# A-Power.net
KiCad netlist of a schematic drawn in Altium Designer
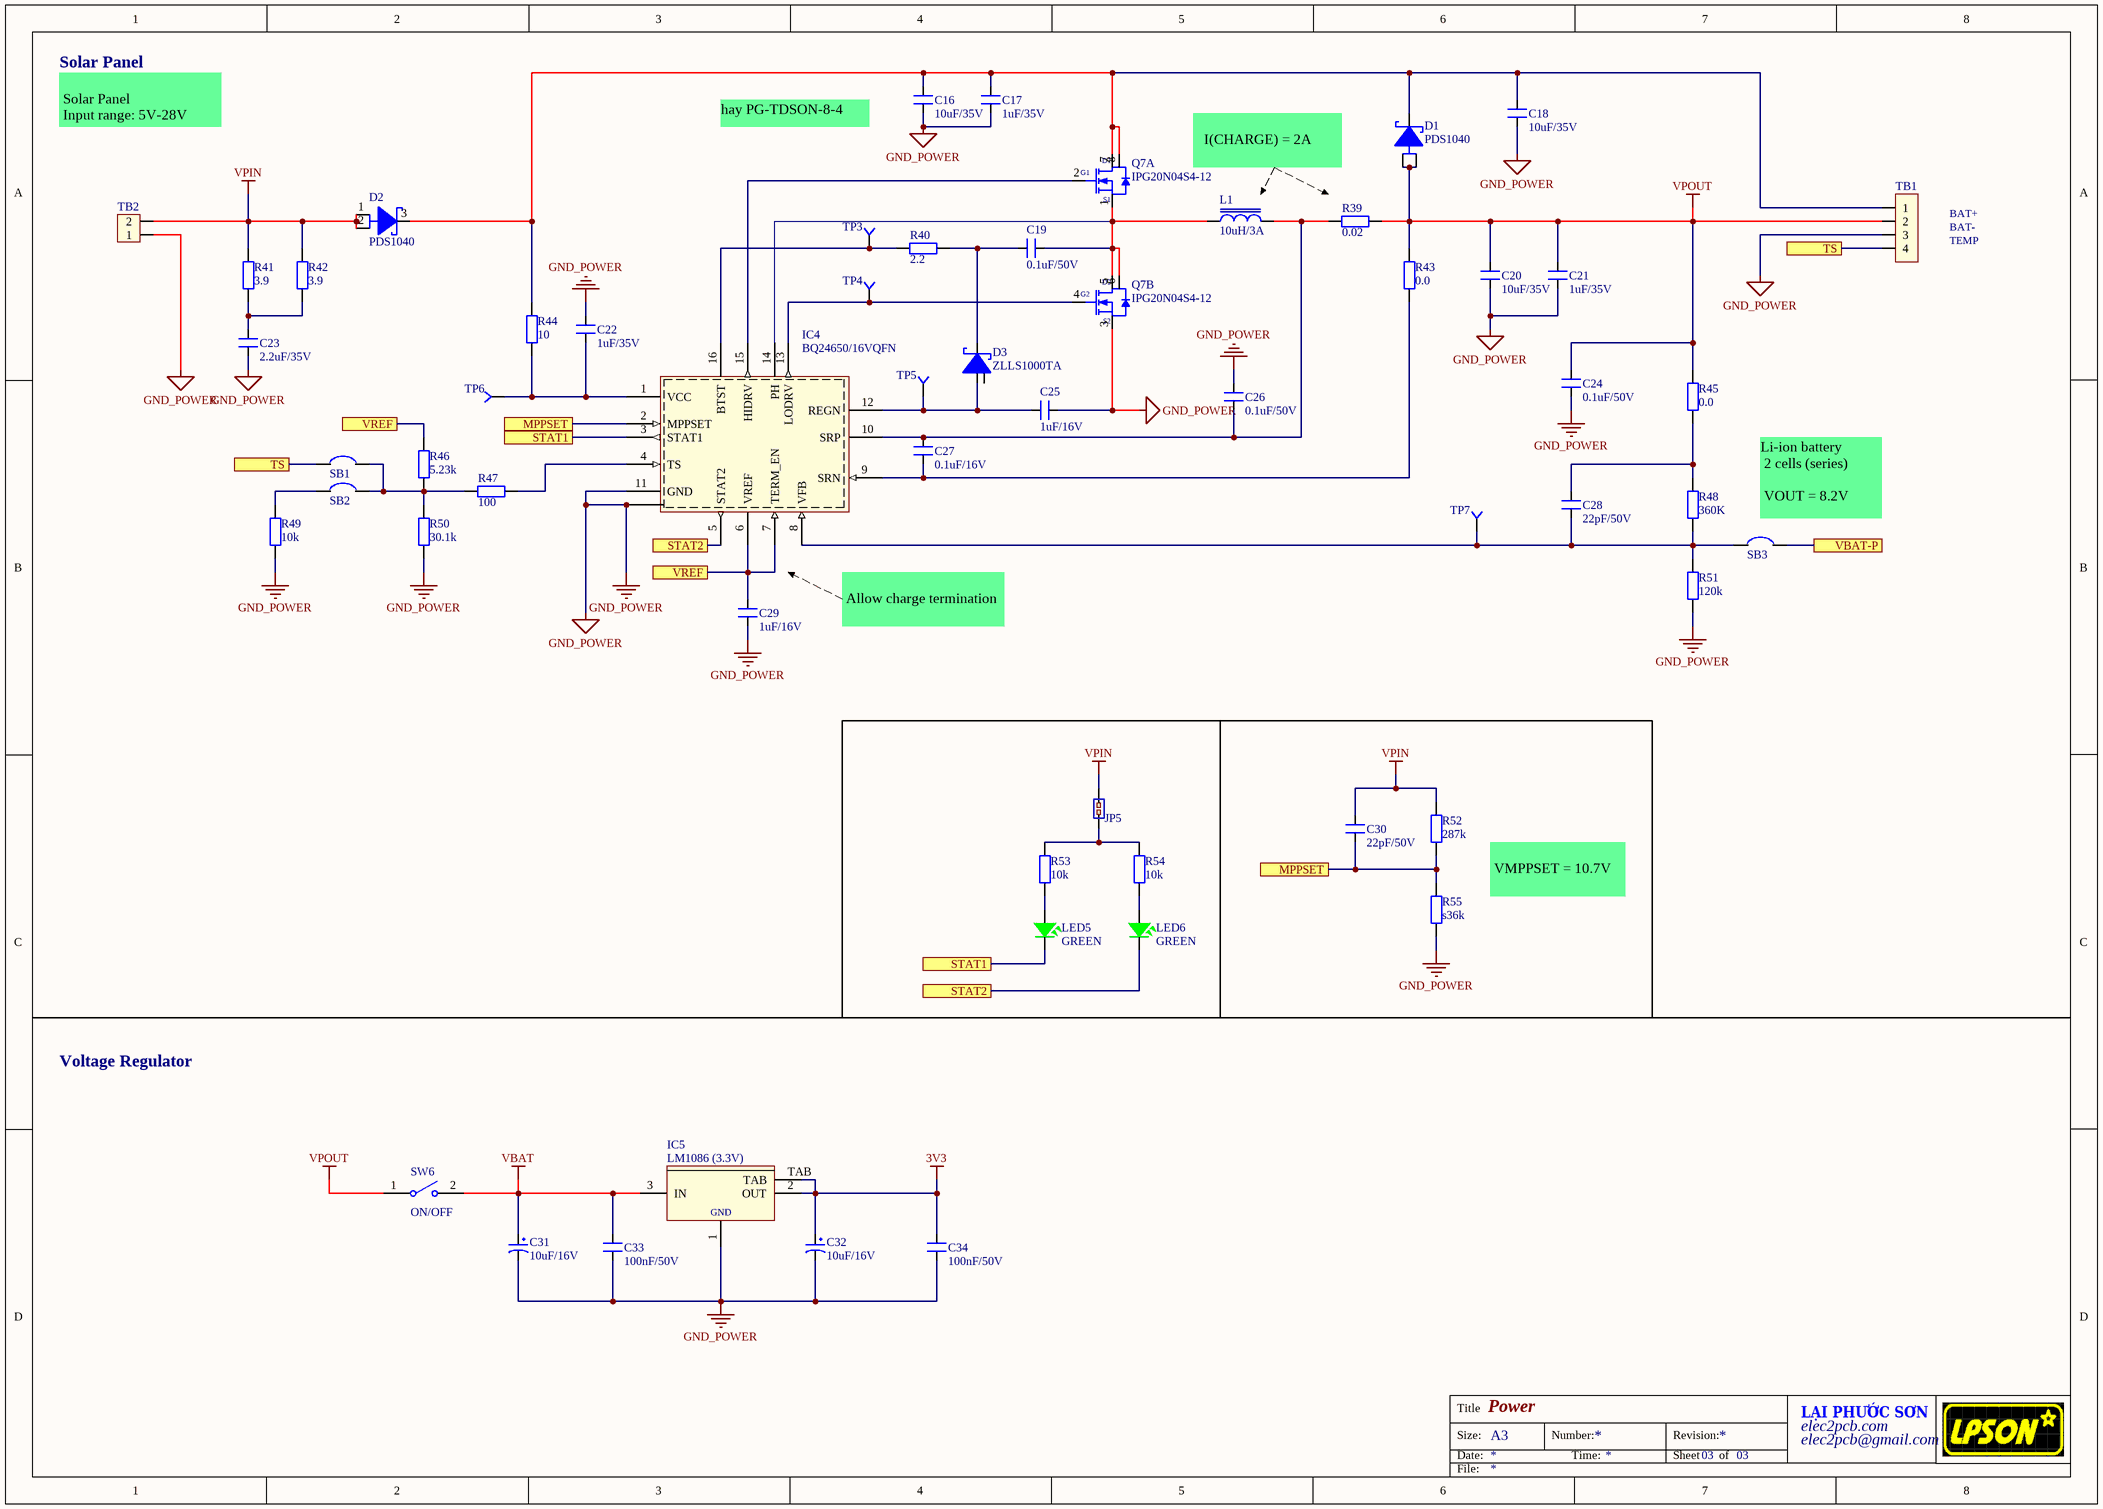
[diagram p0: A-Power.SchDoc]

(export (version "E")
  (design (tool "Eeschema 10.0.6"))
  (components
    (comp (ref "C16")
      (value "10uF/35V")
      (footprint "CAP_CERA_C3216(CC1206INCH)")
      (description "CAP CER 10UF 35V X7R 1206")
      (fields
        (field (name "MANUFACTURER") "Taiyo Yuden")
        (field (name "MANUFACTURER PART NUMBER") "GMK316AB7106KL-TR")
      )
      (libsource (lib "Tran Tuan") (part "CAP-CER/10uF/35V/X7R-1206"))
    )
    (comp (ref "C17")
      (value "1uF/35V")
      (footprint "CAP_CERA_C2012(CC0805INCH)")
      (description "CAP CER 1UF 35V X7R 0805")
      (fields
        (field (name "MANUFACTURER") "Taiyo Yuden")
        (field (name "MANUFACTURER PART NUMBER") "GMK212B7105KG-T")
      )
      (libsource (lib "Tran Tuan") (part "CAP-CER/1uF/35V/X7R/0805"))
    )
    (comp (ref "C18")
      (value "10uF/35V")
      (footprint "CAP_CERA_C3216(CC1206INCH)")
      (description "CAP CER 10UF 35V X7R 1206")
      (fields
        (field (name "MANUFACTURER") "Taiyo Yuden")
        (field (name "MANUFACTURER PART NUMBER") "GMK316AB7106KL-TR")
      )
      (libsource (lib "Tran Tuan") (part "CAP-CER/10uF/35V/X7R-1206"))
    )
    (comp (ref "C19")
      (value "0.1uF/50V")
      (footprint "CAP_CERA_C1608(CC0603INCH)")
      (description "CAP CER 0.1UF 50V X7R 0603")
      (fields
        (field (name "MANUFACTURER") "Kemet")
        (field (name "MANUFACTURER PART NUMBER") "C0603X104K5RACTU")
      )
      (libsource (lib "Tran Tuan") (part "CAP-CER/0.1uF/50V/X7R/0603"))
    )
    (comp (ref "C20")
      (value "10uF/35V")
      (footprint "CAP_CERA_C3216(CC1206INCH)")
      (description "CAP CER 10UF 35V X7R 1206")
      (fields
        (field (name "MANUFACTURER") "Taiyo Yuden")
        (field (name "MANUFACTURER PART NUMBER") "GMK316AB7106KL-TR")
      )
      (libsource (lib "Tran Tuan") (part "CAP-CER/10uF/35V/X7R-1206"))
    )
    (comp (ref "C21")
      (value "1uF/35V")
      (footprint "CAP_CERA_C2012(CC0805INCH)")
      (description "CAP CER 1UF 35V X7R 0805")
      (fields
        (field (name "MANUFACTURER") "Taiyo Yuden")
        (field (name "MANUFACTURER PART NUMBER") "GMK212B7105KG-T")
      )
      (libsource (lib "Tran Tuan") (part "CAP-CER/1uF/35V/X7R/0805"))
    )
    (comp (ref "C22")
      (value "1uF/35V")
      (footprint "CAP_CERA_C2012(CC0805INCH)")
      (description "CAP CER 1UF 35V X7R 0805")
      (fields
        (field (name "MANUFACTURER") "Taiyo Yuden")
        (field (name "MANUFACTURER PART NUMBER") "GMK212B7105KG-T")
      )
      (libsource (lib "Tran Tuan") (part "CAP-CER/1uF/35V/X7R/0805"))
    )
    (comp (ref "C23")
      (value "2.2uF/35V")
      (footprint "CAP_CERA_C3225(CC1210)")
      (description "CAP CER 2.2UF 35V X7R 1210")
      (fields
        (field (name "MANUFACTURER") "Taiyo Yuden")
        (field (name "MANUFACTURER PART NUMBER") "GMK325B7225KNHT")
      )
      (libsource (lib "Tran Tuan") (part "CAP-CER/2.2uF/35V/X7R/1210"))
    )
    (comp (ref "C24")
      (value "0.1uF/50V")
      (footprint "CAP_CERA_C1608(CC0603INCH)")
      (description "CAP CER 0.1UF 50V X7R 0603")
      (fields
        (field (name "MANUFACTURER") "Kemet")
        (field (name "MANUFACTURER PART NUMBER") "C0603X104K5RACTU")
      )
      (libsource (lib "Tran Tuan") (part "CAP-CER/0.1uF/50V/X7R/0603"))
    )
    (comp (ref "C25")
      (value "1uF/16V")
      (footprint "CAP_CERA_C2012(CC0805INCH)")
      (description "CAP CER 1UF 16V X7R 0805")
      (fields
        (field (name "MANUFACTURER") "Kemet")
        (field (name "MANUFACTURER PART NUMBER") "C0805C105K4RACTU")
      )
      (libsource (lib "Tran Tuan") (part "CAP-CER/1uF/16V/X7R/0805"))
    )
    (comp (ref "C26")
      (value "0.1uF/50V")
      (footprint "CAP_CERA_C1608(CC0603INCH)")
      (description "CAP CER 0.1UF 50V X7R 0603")
      (fields
        (field (name "MANUFACTURER") "Kemet")
        (field (name "MANUFACTURER PART NUMBER") "C0603X104K5RACTU")
      )
      (libsource (lib "Tran Tuan") (part "CAP-CER/0.1uF/50V/X7R/0603"))
    )
    (comp (ref "C27")
      (value "0.1uF/16V")
      (footprint "CAP_CERA_C1608(CC0603INCH)")
      (description "CAP CER 0.1UF 16V X7R 0603")
      (fields
        (field (name "MANUFACTURER") "Yageo")
        (field (name "MANUFACTURER PART NUMBER") "CC0603KRX7R7BB104")
      )
      (libsource (lib "Tran Tuan") (part "CAP-CER/0.1uF/16V/X7R/0603"))
    )
    (comp (ref "C28")
      (value "22pF/50V")
      (footprint "CAP_CERA_C1608(CC0603INCH)")
      (description "CAP CER 22PF 50V X7R 0603")
      (fields
        (field (name "MANUFACTURER") "AVX Corporation")
        (field (name "MANUFACTURER PART NUMBER") "06035C220JAT2A")
      )
      (libsource (lib "Tran Tuan") (part "CAP-CER/22pF/50V/X7R/0603"))
    )
    (comp (ref "C29")
      (value "1uF/16V")
      (footprint "CAP_CERA_C2012(CC0805INCH)")
      (description "CAP CER 1UF 16V X7R 0805")
      (fields
        (field (name "MANUFACTURER") "Kemet")
        (field (name "MANUFACTURER PART NUMBER") "C0805C105K4RACTU")
      )
      (libsource (lib "Tran Tuan") (part "CAP-CER/1uF/16V/X7R/0805"))
    )
    (comp (ref "C30")
      (value "22pF/50V")
      (footprint "CAP_CERA_C1608(CC0603INCH)")
      (description "CAP CER 22PF 50V X7R 0603")
      (fields
        (field (name "MANUFACTURER") "AVX Corporation")
        (field (name "MANUFACTURER PART NUMBER") "06035C220JAT2A")
      )
      (libsource (lib "Tran Tuan") (part "CAP-CER/22pF/50V/X7R/0603"))
    )
    (comp (ref "C31")
      (value "10uF/16V")
      (footprint "CAP_CERA_C3216(CC1206INCH)")
      (description "CAP TANT 10UF 16V 10% 1206")
      (fields
        (field (name "MANUFACTURER") "Kemet")
        (field (name "MANUFACTURER PART NUMBER") "T491A106K016AT")
      )
      (libsource (lib "Tran Tuan") (part "CAP-TANT/10uF/16V/1206"))
    )
    (comp (ref "C32")
      (value "10uF/16V")
      (footprint "CAP_CERA_C3216(CC1206INCH)")
      (description "CAP TANT 10UF 16V 10% 1206")
      (fields
        (field (name "MANUFACTURER") "Kemet")
        (field (name "MANUFACTURER PART NUMBER") "T491A106K016AT")
      )
      (libsource (lib "Tran Tuan") (part "CAP-TANT/10uF/16V/1206"))
    )
    (comp (ref "C33")
      (value "100nF/50V")
      (footprint "CAP_CERA_C2012(CC0805INCH)")
      (description "CAP CER 0.1UF 50V X7R 0805")
      (fields
        (field (name "MANUFACTURER") "AVX Corporation")
        (field (name "MANUFACTURER PART NUMBER") "08055C104KAT2A")
      )
      (libsource (lib "Tran Tuan") (part "CAP-CER/100nF/50V/X7R-0805"))
    )
    (comp (ref "C34")
      (value "100nF/50V")
      (footprint "CAP_CERA_C2012(CC0805INCH)")
      (description "CAP CER 0.1UF 50V X7R 0805")
      (fields
        (field (name "MANUFACTURER") "AVX Corporation")
        (field (name "MANUFACTURER PART NUMBER") "08055C104KAT2A")
      )
      (libsource (lib "Tran Tuan") (part "CAP-CER/100nF/50V/X7R-0805"))
    )
    (comp (ref "D1")
      (value "PDS1040")
      (footprint "PDS1040")
      (description "DIODE SCHOTTKY 40V 10A POWERDI5")
      (fields
        (field (name "MANUFACTURER") "Diodes Incorporated")
        (field (name "MANUFACTURER PART NUMBER") "PDS1040-13")
      )
      (libsource (lib "") (part "DIODE-PDS1040/POWERDI5_1"))
    )
    (comp (ref "D2")
      (value "PDS1040")
      (footprint "PDS1040")
      (description "DIODE SCHOTTKY 40V 10A POWERDI5")
      (fields
        (field (name "MANUFACTURER") "Diodes Incorporated")
        (field (name "MANUFACTURER PART NUMBER") "PDS1040-13")
      )
      (libsource (lib "Tran Tuan") (part "DIODE-PDS1040/POWERDI5"))
    )
    (comp (ref "D3")
      (value "ZLLS1000TA")
      (footprint "ZLLS1000")
      (description "DIODE SCHOTTKY 40V 1.16A SOT23-3")
      (fields (field (name "MANUFACTURER") "Diodes Incorporated"))
      (libsource (lib "Tran Tuan") (part "DIODE-ZLLS1000TA/SOT23-3"))
    )
    (comp (ref "IC4")
      (value "BQ24650/16VQFN")
      (footprint "BQ24650-16VQFN")
      (description "IC SYNC SW-MODE BAT CHRGR 16VQFN")
      (fields
        (field (name "MANUFACTURER") "Texas Instruments")
        (field (name "MANUFACTURER PART NUMBER") "BQ24650RVAT")
      )
      (libsource (lib "Tran Tuan") (part "BQ24650/16VQFN"))
    )
    (comp (ref "IC5")
      (value "LM1086 (3.3V)")
      (footprint "LM1086")
      (description "IC REG LDO 3.3V 1.5A DDPAK")
      (fields
        (field (name "MANUFACTURER") "Texas Instruments")
        (field (name "MANUFACTURER PART NUMBER") "LM1086CS-3.3/NOPB")
      )
      (libsource (lib "Tran Tuan") (part "LM1086CS-3.3/NOPB"))
    )
    (comp (ref "JP5")
      (value "JP2-ShortingJumper")
      (footprint "Header_2")
      (description "2.54mm 2-Pin Shorting Jumper")
      (libsource (lib "Tran Tuan") (part "JP2-ShortingJumper"))
    )
    (comp (ref "L1")
      (value "10uH/3A")
      (footprint "IHLP-2525CZ-01")
      (description "FIXED IND 10UH 3A 105mOHM SMD")
      (fields
        (field (name "MANUFACTURER") "Vishay Dale")
        (field (name "MANUFACTURER PART NUMBER") "IHLP2525CZER100M01")
      )
      (libsource (lib "Tran Tuan") (part "IND-10uH/3A/105mOHM"))
    )
    (comp (ref "LED5")
      (value "GREEN")
      (footprint "Led 0805G")
      (description "LED GREEN CLEAR 0805 SMD")
      (fields
        (field (name "MANUFACTURER") "Lite-On Inc.")
        (field (name "MANUFACTURER PART NUMBER") "LTST-C171GKT")
      )
      (libsource (lib "Tran Tuan") (part "LED-GREEN/CLEAR/0805"))
    )
    (comp (ref "LED6")
      (value "GREEN")
      (footprint "Led 0805G")
      (description "LED GREEN CLEAR 0805 SMD")
      (fields
        (field (name "MANUFACTURER") "Lite-On Inc.")
        (field (name "MANUFACTURER PART NUMBER") "LTST-C171GKT")
      )
      (libsource (lib "Tran Tuan") (part "LED-GREEN/CLEAR/0805"))
    )
    (comp (ref "Q7")
      (value "IPG20N04S4-12")
      (footprint "PG-TDSON-8-4")
      (description "MOSFE,T 2N-CH, 40V 20A TDSON-8 OptiMOS-T2")
      (fields (field (name "MANUFACTURER") "Infineon"))
      (libsource (lib "Tran Tuan") (part "MOSFET-IPG20N04S4/TDSON8"))
    )
    (comp (ref "R39")
      (value "~")
      (footprint "RES-1206-3216MM")
      (description "RES SMD 0.02 OHM 1% 1W 1206")
      (fields
        (field (name "MANUFACTURER") "Vishay Dale")
        (field (name "MANUFACTURER PART NUMBER") "WSLP1206R0200FEA")
        (field (name "RESISTANCE (OHMS)") "0.02")
      )
      (libsource (lib "Tran Tuan") (part "RES-1206/±1%"))
    )
    (comp (ref "R40")
      (value "~")
      (footprint "RESC2012(0805)")
      (description "RES SMD 2.2 OHM 5% 1/8W 0805")
      (fields
        (field (name "MANUFACTURER") "Panasonic Electronic Components")
        (field (name "MANUFACTURER PART NUMBER") "ERJ-6GEYJ2R2V")
        (field (name "RESISTANCE (OHMS)") "2.2")
      )
      (libsource (lib "") (part "RES-0805/±5%_1"))
    )
    (comp (ref "R41")
      (value "~")
      (footprint "RES-1206-3216MM")
      (description "RES SMD 3.9 OHM 1% 1/4W 1206")
      (fields
        (field (name "MANUFACTURER") "Panasonic Electronic Components")
        (field (name "MANUFACTURER PART NUMBER") "ERJ-8RQF3R9V")
        (field (name "RESISTANCE (OHMS)") "3.9")
      )
      (libsource (lib "Tran Tuan") (part "RES-1206/±5%"))
    )
    (comp (ref "R42")
      (value "~")
      (footprint "RES-1206-3216MM")
      (description "RES SMD 3.9 OHM 1% 1/4W 1206")
      (fields
        (field (name "MANUFACTURER") "Panasonic Electronic Components")
        (field (name "MANUFACTURER PART NUMBER") "ERJ-8RQF3R9V")
        (field (name "RESISTANCE (OHMS)") "3.9")
      )
      (libsource (lib "Tran Tuan") (part "RES-1206/±5%"))
    )
    (comp (ref "R43")
      (value "~")
      (footprint "RESC2012(0805)")
      (description "RES SMD 0.0 OHM JUMPER 1/8W 0805")
      (fields
        (field (name "MANUFACTURER") "Yageo")
        (field (name "MANUFACTURER PART NUMBER") "RC0805JR-070RL")
        (field (name "RESISTANCE (OHMS)") "0.0")
      )
      (libsource (lib "Tran Tuan") (part "RES-0805/±5%"))
    )
    (comp (ref "R44")
      (value "~")
      (footprint "RESC2012(0805)")
      (description "RES SMD 10 OHM 5% 1/8W 0805")
      (fields
        (field (name "MANUFACTURER") "Yageo")
        (field (name "MANUFACTURER PART NUMBER") "RC0805JR-0710RL")
        (field (name "RESISTANCE (OHMS)") "10")
      )
      (libsource (lib "Tran Tuan") (part "RES-0805/±5%"))
    )
    (comp (ref "R45")
      (value "~")
      (footprint "RESC2012(0805)")
      (description "RES SMD 0.0 OHM JUMPER 1/8W 0805")
      (fields
        (field (name "MANUFACTURER") "Yageo")
        (field (name "MANUFACTURER PART NUMBER") "RC0805JR-070RL")
        (field (name "RESISTANCE (OHMS)") "0.0")
      )
      (libsource (lib "Tran Tuan") (part "RES-0805/±5%"))
    )
    (comp (ref "R46")
      (value "~")
      (footprint "RESC2012(0805)")
      (description "RES SMD 5.23K OHM 1% 1/8W 0805")
      (fields
        (field (name "MANUFACTURER") "Panasonic Electronic Components")
        (field (name "MANUFACTURER PART NUMBER") "ERJ-6ENF5231V")
        (field (name "RESISTANCE (OHMS)") "5.23k")
      )
      (libsource (lib "") (part "RES-0805/±1%_1"))
    )
    (comp (ref "R47")
      (value "~")
      (footprint "RESC2012(0805)")
      (description "RES SMD 100 OHM 5% 1/8W 0805")
      (fields
        (field (name "MANUFACTURER") "Panasonic Electronic Components")
        (field (name "MANUFACTURER PART NUMBER") "ERJ-6GEYJ101V")
        (field (name "RESISTANCE (OHMS)") "100")
      )
      (libsource (lib "") (part "RES-0805/±5%_1"))
    )
    (comp (ref "R48")
      (value "360K")
      (footprint "RESC2012(0805)")
      (description "RES SMD 360K OHM 1% 1/8W 0805")
      (fields
        (field (name "MANUFACTURER") "Yageo")
        (field (name "MANUFACTURER PART NUMBER") "RC0805FR-07360KL")
      )
      (libsource (lib "Tran Tuan") (part "RES-0805/±1%"))
    )
    (comp (ref "R49")
      (value "~")
      (footprint "RESC2012(0805)")
      (description "RES SMD 10K OHM 5% 1/8W 0805")
      (fields
        (field (name "MANUFACTURER") "Yageo")
        (field (name "MANUFACTURER PART NUMBER") "RC0805JR-0710KL")
        (field (name "RESISTANCE (OHMS)") "10k")
      )
      (libsource (lib "Tran Tuan") (part "RES-0805/±5%"))
    )
    (comp (ref "R50")
      (value "~")
      (footprint "RESC2012(0805)")
      (description "RES SMD 30.1K OHM 1% 1/8W 0805")
      (fields
        (field (name "MANUFACTURER") "Yageo")
        (field (name "MANUFACTURER PART NUMBER") "RC0805FR-0730K1L")
        (field (name "RESISTANCE (OHMS)") "30.1k")
      )
      (libsource (lib "") (part "RES-0805/±1%_1"))
    )
    (comp (ref "R51")
      (value "~")
      (footprint "RESC2012(0805)")
      (description "RES SMD 120K OHM 1% 1/8W 0805")
      (fields
        (field (name "MANUFACTURER") "Yageo")
        (field (name "MANUFACTURER PART NUMBER") "RC0805FR-07120KL")
        (field (name "RESISTANCE (OHMS)") "120k")
      )
      (libsource (lib "") (part "RES-0805/±1%_1"))
    )
    (comp (ref "R52")
      (value "~")
      (footprint "RESC2012(0805)")
      (description "RES SMD 287K OHM 1% 1/8W 0805")
      (fields
        (field (name "MANUFACTURER") "Panasonic Electronic Components")
        (field (name "MANUFACTURER PART NUMBER") "ERJ-6ENF2873V")
        (field (name "RESISTANCE (OHMS)") "287k")
      )
      (libsource (lib "") (part "RES-0805/±1%_1"))
    )
    (comp (ref "R53")
      (value "~")
      (footprint "RESC2012(0805)")
      (description "RES SMD 10K OHM 5% 1/8W 0805")
      (fields
        (field (name "MANUFACTURER") "Yageo")
        (field (name "MANUFACTURER PART NUMBER") "RC0805JR-0710KL")
        (field (name "RESISTANCE (OHMS)") "10k")
      )
      (libsource (lib "Tran Tuan") (part "RES-0805/±5%"))
    )
    (comp (ref "R54")
      (value "~")
      (footprint "RESC2012(0805)")
      (description "RES SMD 10K OHM 5% 1/8W 0805")
      (fields
        (field (name "MANUFACTURER") "Yageo")
        (field (name "MANUFACTURER PART NUMBER") "RC0805JR-0710KL")
        (field (name "RESISTANCE (OHMS)") "10k")
      )
      (libsource (lib "Tran Tuan") (part "RES-0805/±5%"))
    )
    (comp (ref "R55")
      (value "~")
      (footprint "RESC2012(0805)")
      (description "RES SMD 36K OHM 1% 1/8W 0805")
      (fields
        (field (name "MANUFACTURER") "Panasonic Electronic Components")
        (field (name "MANUFACTURER PART NUMBER") "ERJ-6ENF3602V")
        (field (name "RESISTANCE (OHMS)") "s36k")
      )
      (libsource (lib "Tran Tuan") (part "RES-0805/±1%"))
    )
    (comp (ref "SB1")
      (value "Connect")
      (footprint "head PAD")
      (description "Jumper, Connector, 2-pad")
      (libsource (lib "Tran Tuan") (part "Connector-SB"))
    )
    (comp (ref "SB2")
      (value "Connect")
      (footprint "head PAD")
      (description "Jumper, Connector, 2-pad")
      (libsource (lib "Tran Tuan") (part "Connector-SB"))
    )
    (comp (ref "SB3")
      (value "Connect")
      (footprint "head PAD")
      (description "Jumper, Connector, 2-pad")
      (libsource (lib "Tran Tuan") (part "Connector-SB"))
    )
    (comp (ref "SW6")
      (value "ON/OFF")
      (footprint "SW-POWER")
      (description "SWITCH ROCKER SPST 16A 125V")
      (fields
        (field (name "MANUFACTURER") "TE Connectivity Alcoswitch Switches")
        (field (name "MANUFACTURER PART NUMBER") "PRASA1-16F-BB0BW")
      )
      (libsource (lib "Tran Tuan") (part "SW-ROCKER/SPST/16A"))
    )
    (comp (ref "TB1")
      (value "TERM BLOCK")
      (footprint "MKDS-DOMINO-4-PIN")
      (description "TERM BLOCK 4POS 3.81MM PCB GRN")
      (fields
        (field (name "MANUFACTURER") "Phoenix Contact")
        (field (name "MANUFACTURER PART NUMBER") "1727036")
      )
      (libsource (lib "Tran Tuan") (part "TERM/3.81MM/4POS/GREEN"))
    )
    (comp (ref "TB2")
      (value "TERM BLOCK")
      (footprint "MKDS-DOMINO-2-PIN")
      (description "TERM BLOCK 2POS 3.81MM PCB GRN")
      (fields
        (field (name "MANUFACTURER") "Phoenix Contact")
        (field (name "MANUFACTURER PART NUMBER") "1727010")
      )
      (libsource (lib "Tran Tuan") (part "TERM/3.81MM/2POS/GREEN"))
    )
    (comp (ref "TP3")
      (value "Test Point")
      (footprint "Test_point_VIA06")
      (description "Test Point, Pad, Hole")
      (libsource (lib "Tran Tuan") (part "Connector-TP"))
    )
    (comp (ref "TP4")
      (value "Test Point")
      (footprint "Test_point_VIA06")
      (description "Test Point, Pad, Hole")
      (libsource (lib "Tran Tuan") (part "Connector-TP"))
    )
    (comp (ref "TP5")
      (value "Test Point")
      (footprint "Test_point_VIA06")
      (description "Test Point, Pad, Hole")
      (libsource (lib "Tran Tuan") (part "Connector-TP"))
    )
    (comp (ref "TP6")
      (value "Test Point")
      (footprint "Test_point_VIA06")
      (description "Test Point, Pad, Hole")
      (libsource (lib "Tran Tuan") (part "Connector-TP"))
    )
    (comp (ref "TP7")
      (value "Test Point")
      (footprint "Test_point_VIA06")
      (description "Test Point, Pad, Hole")
      (libsource (lib "Tran Tuan") (part "Connector-TP"))
    )
  )
  (nets
    (net (code "1") (name "/MPPSET") (class "Default")
      (node (ref "C30") (pin "2") (pinfunction "2_2") (pintype "passive"))
      (node (ref "IC4") (pin "2") (pinfunction "MPPSET_2") (pintype "input"))
      (node (ref "R52") (pin "2") (pinfunction "2_2") (pintype "passive"))
      (node (ref "R55") (pin "2") (pinfunction "2_2") (pintype "passive"))
    )
    (net (code "2") (name "/STAT1") (class "Default")
      (node (ref "IC4") (pin "3") (pinfunction "STAT1_3") (pintype "output"))
      (node (ref "LED5") (pin "2") (pinfunction "K_2") (pintype "passive"))
    )
    (net (code "3") (name "/STAT2") (class "Default")
      (node (ref "IC4") (pin "5") (pinfunction "STAT2_5") (pintype "output"))
      (node (ref "LED6") (pin "2") (pinfunction "K_2") (pintype "passive"))
    )
    (net (code "4") (name "/TS") (class "Default")
      (node (ref "SB1") (pin "2") (pinfunction "2_2") (pintype "passive"))
      (node (ref "TB1") (pin "4") (pinfunction "4_4") (pintype "passive"))
    )
    (net (code "5") (name "/VBAT-P") (class "Default")
      (node (ref "SB3") (pin "1") (pinfunction "1_1") (pintype "passive"))
    )
    (net (code "6") (name "/VREF") (class "Default")
      (node (ref "C29") (pin "2") (pinfunction "2_2") (pintype "passive"))
      (node (ref "IC4") (pin "6") (pinfunction "VREF_6") (pintype "power_in"))
      (node (ref "IC4") (pin "7") (pinfunction "TERM_EN_7") (pintype "input"))
      (node (ref "R46") (pin "1") (pinfunction "1_1") (pintype "passive"))
    )
    (net (code "7") (name "3V3") (class "Default")
      (node (ref "C32") (pin "1") (pinfunction "1_1") (pintype "passive"))
      (node (ref "C34") (pin "1") (pinfunction "1_1") (pintype "passive"))
      (node (ref "IC5") (pin "2") (pinfunction "OUT_2") (pintype "power_in"))
      (node (ref "IC5") (pin "TAB") (pinfunction "TAB_TAB") (pintype "power_in"))
    )
    (net (code "8") (name "GND_POWER") (class "Default")
      (node (ref "C16") (pin "2") (pinfunction "2_2") (pintype "passive"))
      (node (ref "C17") (pin "2") (pinfunction "2_2") (pintype "passive"))
      (node (ref "C18") (pin "2") (pinfunction "2_2") (pintype "passive"))
      (node (ref "C20") (pin "2") (pinfunction "2_2") (pintype "passive"))
      (node (ref "C21") (pin "2") (pinfunction "2_2") (pintype "passive"))
      (node (ref "C22") (pin "2") (pinfunction "2_2") (pintype "passive"))
      (node (ref "C23") (pin "2") (pinfunction "2_2") (pintype "passive"))
      (node (ref "C24") (pin "1") (pinfunction "1_1") (pintype "passive"))
      (node (ref "C25") (pin "1") (pinfunction "1_1") (pintype "passive"))
      (node (ref "C26") (pin "2") (pinfunction "2_2") (pintype "passive"))
      (node (ref "C29") (pin "1") (pinfunction "1_1") (pintype "passive"))
      (node (ref "C31") (pin "2") (pinfunction "2_2") (pintype "passive"))
      (node (ref "C32") (pin "2") (pinfunction "2_2") (pintype "passive"))
      (node (ref "C33") (pin "2") (pinfunction "2_2") (pintype "passive"))
      (node (ref "C34") (pin "2") (pinfunction "2_2") (pintype "passive"))
      (node (ref "IC4") (pin "11") (pinfunction "GND_11") (pintype "power_in"))
      (node (ref "IC4") (pin "PAD") (pinfunction "PAD_PAD") (pintype "power_in"))
      (node (ref "IC5") (pin "1") (pinfunction "GND_1") (pintype "power_in"))
      (node (ref "Q7") (pin "3") (pinfunction "S2_3") (pintype "passive"))
      (node (ref "R49") (pin "2") (pinfunction "2_2") (pintype "passive"))
      (node (ref "R50") (pin "2") (pinfunction "2_2") (pintype "passive"))
      (node (ref "R51") (pin "2") (pinfunction "2_2") (pintype "passive"))
      (node (ref "R55") (pin "1") (pinfunction "1_1") (pintype "passive"))
      (node (ref "TB1") (pin "3") (pinfunction "3_3") (pintype "passive"))
      (node (ref "TB2") (pin "1") (pinfunction "1_1") (pintype "passive"))
    )
    (net (code "9") (name "Net-(C23-Pad1)") (class "Default")
      (node (ref "C23") (pin "1") (pinfunction "1_1") (pintype "passive"))
      (node (ref "R41") (pin "2") (pinfunction "2_2") (pintype "passive"))
      (node (ref "R42") (pin "2") (pinfunction "2_2") (pintype "passive"))
    )
    (net (code "10") (name "Net-(C28-Pad1)") (class "Default")
      (node (ref "C28") (pin "1") (pinfunction "1_1") (pintype "passive"))
      (node (ref "R45") (pin "2") (pinfunction "2_2") (pintype "passive"))
      (node (ref "R48") (pin "2") (pinfunction "2_2") (pintype "passive"))
    )
    (net (code "11") (name "Net-(D1-K)") (class "Default")
      (node (ref "C16") (pin "1") (pinfunction "1_1") (pintype "passive"))
      (node (ref "C17") (pin "1") (pinfunction "1_1") (pintype "passive"))
      (node (ref "C18") (pin "1") (pinfunction "1_1") (pintype "passive"))
      (node (ref "D1") (pin "3") (pinfunction "K_3") (pintype "passive"))
      (node (ref "D2") (pin "3") (pinfunction "K_3") (pintype "passive"))
      (node (ref "Q7") (pin "7") (pinfunction "D1_7") (pintype "passive"))
      (node (ref "Q7") (pin "8") (pinfunction "D1_8") (pintype "passive"))
      (node (ref "R44") (pin "1") (pinfunction "1_1") (pintype "passive"))
      (node (ref "TB1") (pin "1") (pinfunction "1_1") (pintype "passive"))
    )
    (net (code "12") (name "Net-(D3-A)") (class "Default")
      (node (ref "C25") (pin "2") (pinfunction "2_2") (pintype "passive"))
      (node (ref "D3") (pin "1") (pinfunction "A_1") (pintype "passive"))
      (node (ref "IC4") (pin "12") (pinfunction "REGN_12") (pintype "power_in"))
      (node (ref "TP5") (pin "1") (pinfunction "1_1") (pintype "passive"))
    )
    (net (code "13") (name "Net-(D3-K)") (class "Default")
      (node (ref "C19") (pin "1") (pinfunction "1_1") (pintype "passive"))
      (node (ref "D3") (pin "3") (pinfunction "K_3") (pintype "passive"))
      (node (ref "R40") (pin "2") (pinfunction "2_2") (pintype "passive"))
    )
    (net (code "14") (name "Net-(IC4-BTST)") (class "Default")
      (node (ref "IC4") (pin "16") (pinfunction "BTST_16") (pintype "power_in"))
      (node (ref "R40") (pin "1") (pinfunction "1_1") (pintype "passive"))
      (node (ref "TP3") (pin "1") (pinfunction "1_1") (pintype "passive"))
    )
    (net (code "15") (name "Net-(IC4-HIDRV)") (class "Default")
      (node (ref "IC4") (pin "15") (pinfunction "HIDRV_15") (pintype "output"))
      (node (ref "Q7") (pin "2") (pinfunction "G1_2") (pintype "passive"))
    )
    (net (code "16") (name "Net-(IC4-LODRV)") (class "Default")
      (node (ref "IC4") (pin "13") (pinfunction "LODRV_13") (pintype "output"))
      (node (ref "Q7") (pin "4") (pinfunction "G2_4") (pintype "passive"))
      (node (ref "TP4") (pin "1") (pinfunction "1_1") (pintype "passive"))
    )
    (net (code "17") (name "Net-(IC4-PH)") (class "Default")
      (node (ref "C19") (pin "2") (pinfunction "2_2") (pintype "passive"))
      (node (ref "IC4") (pin "14") (pinfunction "PH_14") (pintype "power_in"))
      (node (ref "L1") (pin "1") (pinfunction "1_1") (pintype "passive"))
      (node (ref "Q7") (pin "1") (pinfunction "S1_1") (pintype "passive"))
      (node (ref "Q7") (pin "5") (pinfunction "D2_5") (pintype "passive"))
      (node (ref "Q7") (pin "6") (pinfunction "D2_6") (pintype "passive"))
    )
    (net (code "18") (name "Net-(IC4-SRN)") (class "Default")
      (node (ref "C27") (pin "2") (pinfunction "2_2") (pintype "passive"))
      (node (ref "IC4") (pin "9") (pinfunction "SRN_9") (pintype "input"))
      (node (ref "R43") (pin "2") (pinfunction "2_2") (pintype "passive"))
    )
    (net (code "19") (name "Net-(IC4-SRP)") (class "Default")
      (node (ref "C26") (pin "1") (pinfunction "1_1") (pintype "passive"))
      (node (ref "C27") (pin "1") (pinfunction "1_1") (pintype "passive"))
      (node (ref "IC4") (pin "10") (pinfunction "SRP_10") (pintype "passive"))
      (node (ref "L1") (pin "2") (pinfunction "2_2") (pintype "passive"))
      (node (ref "R39") (pin "1") (pinfunction "1_1") (pintype "passive"))
    )
    (net (code "20") (name "Net-(IC4-TS)") (class "Default")
      (node (ref "IC4") (pin "4") (pinfunction "TS_4") (pintype "input"))
      (node (ref "R47") (pin "2") (pinfunction "2_2") (pintype "passive"))
    )
    (net (code "21") (name "Net-(IC4-VCC)") (class "Default")
      (node (ref "C22") (pin "1") (pinfunction "1_1") (pintype "passive"))
      (node (ref "IC4") (pin "1") (pinfunction "VCC_1") (pintype "power_in"))
      (node (ref "R44") (pin "2") (pinfunction "2_2") (pintype "passive"))
      (node (ref "TP6") (pin "1") (pinfunction "1_1") (pintype "passive"))
    )
    (net (code "22") (name "Net-(IC4-VFB)") (class "Default")
      (node (ref "C28") (pin "2") (pinfunction "2_2") (pintype "passive"))
      (node (ref "IC4") (pin "8") (pinfunction "VFB_8") (pintype "input"))
      (node (ref "R48") (pin "1") (pinfunction "1_1") (pintype "passive"))
      (node (ref "R51") (pin "1") (pinfunction "1_1") (pintype "passive"))
      (node (ref "SB3") (pin "2") (pinfunction "2_2") (pintype "passive"))
      (node (ref "TP7") (pin "1") (pinfunction "1_1") (pintype "passive"))
    )
    (net (code "23") (name "Net-(JP5-Pad1)") (class "Default")
      (node (ref "JP5") (pin "1") (pinfunction "1_1") (pintype "passive"))
      (node (ref "R53") (pin "1") (pinfunction "1_1") (pintype "passive"))
      (node (ref "R54") (pin "1") (pinfunction "1_1") (pintype "passive"))
    )
    (net (code "24") (name "Net-(LED5-A)") (class "Default")
      (node (ref "LED5") (pin "1") (pinfunction "A_1") (pintype "passive"))
      (node (ref "R53") (pin "2") (pinfunction "2_2") (pintype "passive"))
    )
    (net (code "25") (name "Net-(LED6-A)") (class "Default")
      (node (ref "LED6") (pin "1") (pinfunction "A_1") (pintype "passive"))
      (node (ref "R54") (pin "2") (pinfunction "2_2") (pintype "passive"))
    )
    (net (code "26") (name "Net-(R46-Pad2)") (class "Default")
      (node (ref "R46") (pin "2") (pinfunction "2_2") (pintype "passive"))
      (node (ref "R47") (pin "1") (pinfunction "1_1") (pintype "passive"))
      (node (ref "R50") (pin "1") (pinfunction "1_1") (pintype "passive"))
      (node (ref "SB1") (pin "1") (pinfunction "1_1") (pintype "passive"))
      (node (ref "SB2") (pin "1") (pinfunction "1_1") (pintype "passive"))
    )
    (net (code "27") (name "Net-(R49-Pad1)") (class "Default")
      (node (ref "R49") (pin "1") (pinfunction "1_1") (pintype "passive"))
      (node (ref "SB2") (pin "2") (pinfunction "2_2") (pintype "passive"))
    )
    (net (code "28") (name "VBAT") (class "Default")
      (node (ref "C31") (pin "1") (pinfunction "1_1") (pintype "passive"))
      (node (ref "C33") (pin "1") (pinfunction "1_1") (pintype "passive"))
      (node (ref "IC5") (pin "3") (pinfunction "IN_3") (pintype "power_in"))
      (node (ref "SW6") (pin "2") (pinfunction "2_2") (pintype "passive"))
    )
    (net (code "29") (name "VPIN") (class "Default")
      (node (ref "C30") (pin "1") (pinfunction "1_1") (pintype "passive"))
      (node (ref "D2") (pin "1") (pinfunction "A1_1") (pintype "passive"))
      (node (ref "D2") (pin "2") (pinfunction "A2_2") (pintype "passive"))
      (node (ref "JP5") (pin "2") (pinfunction "2_2") (pintype "passive"))
      (node (ref "R41") (pin "1") (pinfunction "1_1") (pintype "passive"))
      (node (ref "R42") (pin "1") (pinfunction "1_1") (pintype "passive"))
      (node (ref "R52") (pin "1") (pinfunction "1_1") (pintype "passive"))
      (node (ref "TB2") (pin "2") (pinfunction "2_2") (pintype "passive"))
    )
    (net (code "30") (name "VPOUT") (class "Default")
      (node (ref "C20") (pin "1") (pinfunction "1_1") (pintype "passive"))
      (node (ref "C21") (pin "1") (pinfunction "1_1") (pintype "passive"))
      (node (ref "C24") (pin "2") (pinfunction "2_2") (pintype "passive"))
      (node (ref "D1") (pin "1") (pinfunction "A1_1") (pintype "passive"))
      (node (ref "D1") (pin "2") (pinfunction "A2_2") (pintype "passive"))
      (node (ref "R39") (pin "2") (pinfunction "2_2") (pintype "passive"))
      (node (ref "R43") (pin "1") (pinfunction "1_1") (pintype "passive"))
      (node (ref "R45") (pin "1") (pinfunction "1_1") (pintype "passive"))
      (node (ref "SW6") (pin "1") (pinfunction "1_1") (pintype "passive"))
      (node (ref "TB1") (pin "2") (pinfunction "2_2") (pintype "passive"))
    )
    (net (code "31") (name "unconnected-(D3-PadNC)") (class "Default")
      (node (ref "D3") (pin "NC") (pinfunction "NC_NC") (pintype "tri_state"))
    )
  )
)
